# PIC32.net
KiCad netlist of a schematic drawn in EAGLE
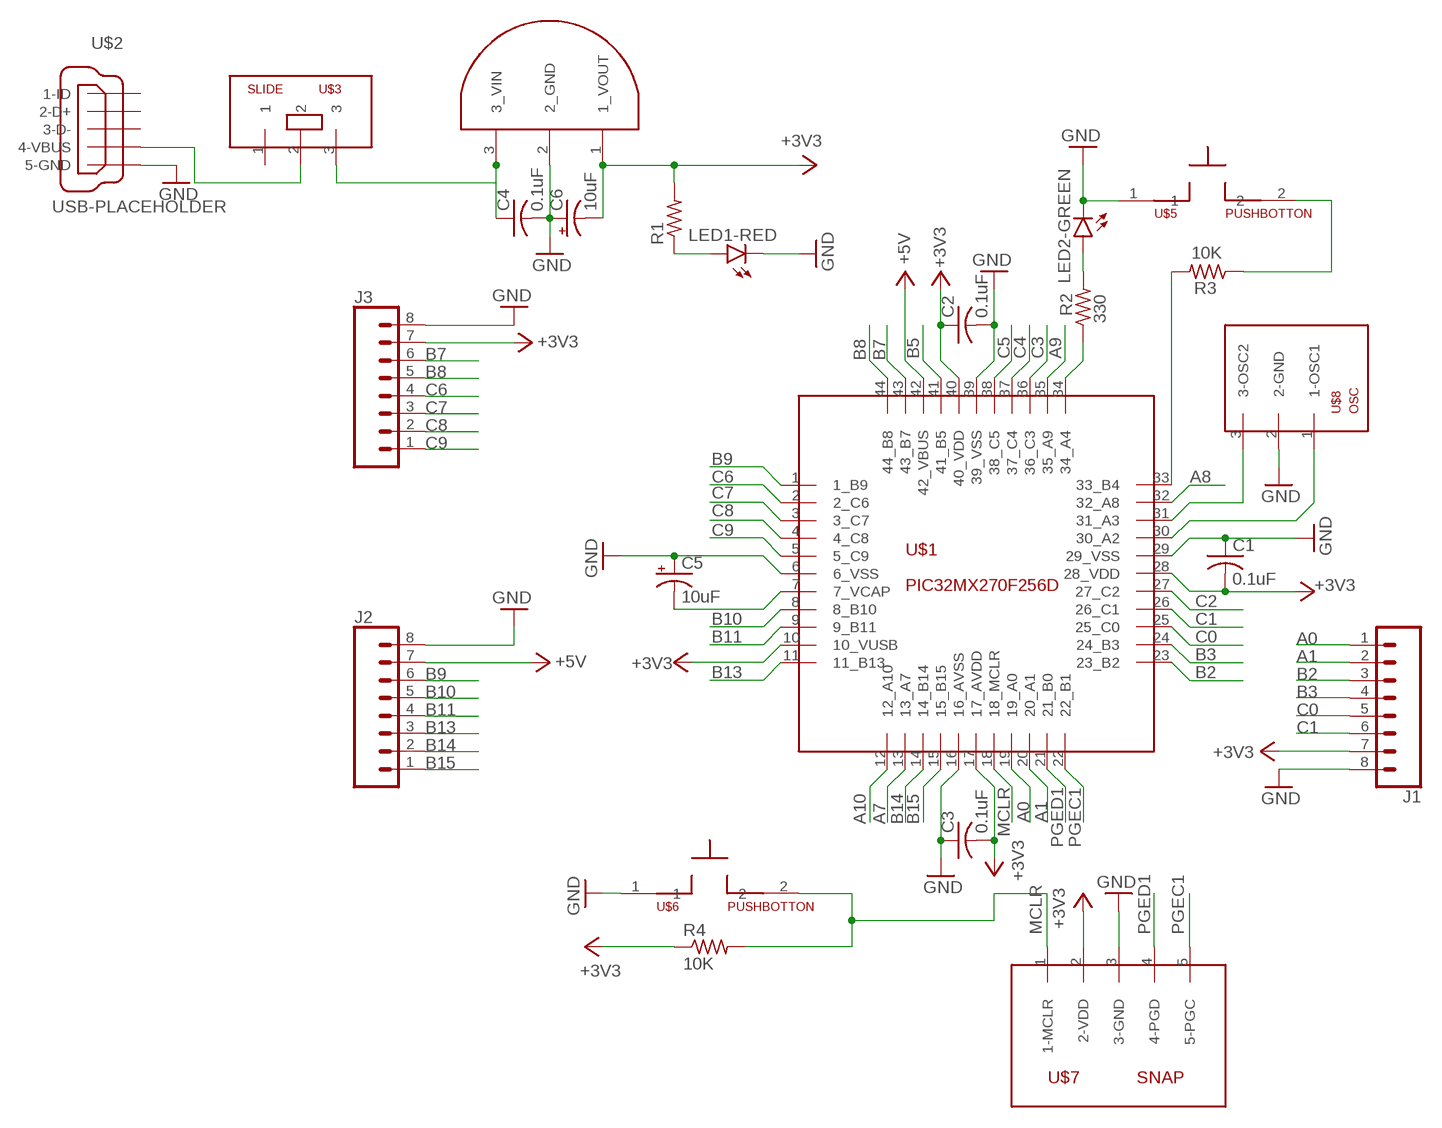
[diagram p0: schematic, sheet 1]

(export (version "E")
  (design (tool "Eeschema 10.0.6"))
  (components
    (comp (ref "C1")
      (value "0.1uF")
      (footprint "eagle-import:C025-025X050")
      (libsource (lib "eagle-import") (part "C-US025-025X050"))
    )
    (comp (ref "C2")
      (value "0.1uF")
      (footprint "eagle-import:C025-025X050")
      (libsource (lib "eagle-import") (part "C-US025-025X050"))
    )
    (comp (ref "C3")
      (value "0.1uF")
      (footprint "eagle-import:C025-025X050")
      (libsource (lib "eagle-import") (part "C-US025-025X050"))
    )
    (comp (ref "C4")
      (value "0.1uF")
      (footprint "eagle-import:C025-025X050")
      (libsource (lib "eagle-import") (part "C-US025-025X050"))
    )
    (comp (ref "C5")
      (value "10uF")
      (footprint "eagle-import:B45181B")
      (libsource (lib "eagle-import") (part "CPOL-USB45181B"))
    )
    (comp (ref "C6")
      (value "10uF")
      (footprint "eagle-import:B45181B")
      (libsource (lib "eagle-import") (part "CPOL-USB45181B"))
    )
    (comp (ref "J1")
      (value "CONN_08\"")
      (footprint "eagle-import:1X08")
      (libsource (lib "eagle-import") (part "CONN_08{dblquote}"))
    )
    (comp (ref "J2")
      (value "CONN_08\"")
      (footprint "eagle-import:1X08")
      (libsource (lib "eagle-import") (part "CONN_08{dblquote}"))
    )
    (comp (ref "J3")
      (value "CONN_08\"")
      (footprint "eagle-import:1X08")
      (libsource (lib "eagle-import") (part "CONN_08{dblquote}"))
    )
    (comp (ref "LED1-RED")
      (value "LED3MM")
      (footprint "eagle-import:LED3MM")
      (libsource (lib "eagle-import") (part "LED3MM"))
    )
    (comp (ref "LED2-GREEN")
      (value "LED3MM")
      (footprint "eagle-import:LED3MM")
      (libsource (lib "eagle-import") (part "LED3MM"))
    )
    (comp (ref "R1")
      (value "R-US_0207/10")
      (footprint "eagle-import:0207_10")
      (libsource (lib "eagle-import") (part "R-US_0207/10"))
    )
    (comp (ref "R2")
      (value "330")
      (footprint "eagle-import:0207_10")
      (libsource (lib "eagle-import") (part "R-US_0207/10"))
    )
    (comp (ref "R3")
      (value "10K")
      (footprint "eagle-import:0207_10")
      (libsource (lib "eagle-import") (part "R-US_0207/10"))
    )
    (comp (ref "R4")
      (value "10K")
      (footprint "eagle-import:0207_10")
      (libsource (lib "eagle-import") (part "R-US_0207/10"))
    )
    (comp (ref "U$1")
      (value "PIC32MX270F256D")
      (footprint "eagle-import:TQFP44")
      (libsource (lib "eagle-import") (part "PIC32MX270F256D"))
    )
    (comp (ref "U$2")
      (value "USB-PLACEHOLDER")
      (footprint "eagle-import:USB-B-MICRO-SMD_V04")
      (libsource (lib "eagle-import") (part "USB-PLACEHOLDER"))
    )
    (comp (ref "U$3")
      (value "SLIDE")
      (footprint "eagle-import:SLIDE")
      (libsource (lib "eagle-import") (part "SLIDE"))
    )
    (comp (ref "U$4")
      (value "L4931")
      (footprint "eagle-import:TO92-")
      (libsource (lib "eagle-import") (part "L4931"))
    )
    (comp (ref "U$5")
      (value "PUSHBOTTON")
      (footprint "eagle-import:PUSHBOTTON")
      (libsource (lib "eagle-import") (part "PUSHBOTTON"))
    )
    (comp (ref "U$6")
      (value "PUSHBOTTON")
      (footprint "eagle-import:PUSHBOTTON")
      (libsource (lib "eagle-import") (part "PUSHBOTTON"))
    )
    (comp (ref "U$7")
      (value "SNAP")
      (footprint "eagle-import:1X05")
      (libsource (lib "eagle-import") (part "SNAP"))
    )
    (comp (ref "U$8")
      (value "OSC")
      (footprint "eagle-import:OSC")
      (libsource (lib "eagle-import") (part "OSC"))
    )
  )
  (nets
    (net (code "1") (name "+3V3") (class "Default")
      (node (ref "C1") (pin "2") (pinfunction "2_2") (pintype "passive"))
      (node (ref "C2") (pin "1") (pinfunction "1_1") (pintype "passive"))
      (node (ref "C3") (pin "2") (pinfunction "2_2") (pintype "passive"))
      (node (ref "C6") (pin "-") (pinfunction "-_-") (pintype "passive"))
      (node (ref "J1") (pin "7") (pinfunction "7_7") (pintype "passive"))
      (node (ref "J3") (pin "7") (pinfunction "7_7") (pintype "passive"))
      (node (ref "R1") (pin "2") (pinfunction "2_2") (pintype "passive"))
      (node (ref "R4") (pin "1") (pinfunction "1_1") (pintype "passive"))
      (node (ref "U$1") (pin "10") (pinfunction "10_VUSB_10") (pintype "bidirectional"))
      (node (ref "U$1") (pin "17") (pinfunction "17_AVDD_17") (pintype "bidirectional"))
      (node (ref "U$1") (pin "28") (pinfunction "28_VDD_28") (pintype "bidirectional"))
      (node (ref "U$1") (pin "40") (pinfunction "40_VDD_40") (pintype "bidirectional"))
      (node (ref "U$4") (pin "1") (pinfunction "1_VOUT_1") (pintype "bidirectional"))
      (node (ref "U$7") (pin "2") (pinfunction "2-VDD_2") (pintype "bidirectional"))
    )
    (net (code "2") (name "+5V") (class "Default")
      (node (ref "J2") (pin "7") (pinfunction "7_7") (pintype "passive"))
      (node (ref "U$1") (pin "42") (pinfunction "42_VBUS_42") (pintype "bidirectional"))
    )
    (net (code "3") (name "/A0") (class "Default")
      (node (ref "J1") (pin "1") (pinfunction "1_1") (pintype "passive"))
      (node (ref "U$1") (pin "19") (pinfunction "19_A0_19") (pintype "bidirectional"))
    )
    (net (code "4") (name "/A1") (class "Default")
      (node (ref "J1") (pin "2") (pinfunction "2_2") (pintype "passive"))
      (node (ref "U$1") (pin "20") (pinfunction "20_A1_20") (pintype "bidirectional"))
    )
    (net (code "5") (name "/A7") (class "Default")
      (node (ref "U$1") (pin "13") (pinfunction "13_A7_13") (pintype "bidirectional"))
    )
    (net (code "6") (name "/A8") (class "Default")
      (node (ref "U$1") (pin "32") (pinfunction "32_A8_32") (pintype "bidirectional"))
    )
    (net (code "7") (name "/A9") (class "Default")
      (node (ref "U$1") (pin "35") (pinfunction "35_A9_35") (pintype "bidirectional"))
    )
    (net (code "8") (name "/A10") (class "Default")
      (node (ref "U$1") (pin "12") (pinfunction "12_A10_12") (pintype "bidirectional"))
    )
    (net (code "9") (name "/B2") (class "Default")
      (node (ref "J1") (pin "3") (pinfunction "3_3") (pintype "passive"))
      (node (ref "U$1") (pin "23") (pinfunction "23_B2_23") (pintype "bidirectional"))
    )
    (net (code "10") (name "/B3") (class "Default")
      (node (ref "J1") (pin "4") (pinfunction "4_4") (pintype "passive"))
      (node (ref "U$1") (pin "24") (pinfunction "24_B3_24") (pintype "bidirectional"))
    )
    (net (code "11") (name "/B5") (class "Default")
      (node (ref "U$1") (pin "41") (pinfunction "41_B5_41") (pintype "bidirectional"))
    )
    (net (code "12") (name "/B7") (class "Default")
      (node (ref "J3") (pin "6") (pinfunction "6_6") (pintype "passive"))
      (node (ref "U$1") (pin "43") (pinfunction "43_B7_43") (pintype "bidirectional"))
    )
    (net (code "13") (name "/B8") (class "Default")
      (node (ref "J3") (pin "5") (pinfunction "5_5") (pintype "passive"))
      (node (ref "U$1") (pin "44") (pinfunction "44_B8_44") (pintype "bidirectional"))
    )
    (net (code "14") (name "/B9") (class "Default")
      (node (ref "J2") (pin "6") (pinfunction "6_6") (pintype "passive"))
      (node (ref "U$1") (pin "1") (pinfunction "1_B9_1") (pintype "bidirectional"))
    )
    (net (code "15") (name "/B10") (class "Default")
      (node (ref "J2") (pin "5") (pinfunction "5_5") (pintype "passive"))
      (node (ref "U$1") (pin "8") (pinfunction "8_B10_8") (pintype "bidirectional"))
    )
    (net (code "16") (name "/B11") (class "Default")
      (node (ref "J2") (pin "4") (pinfunction "4_4") (pintype "passive"))
      (node (ref "U$1") (pin "9") (pinfunction "9_B11_9") (pintype "bidirectional"))
    )
    (net (code "17") (name "/B13") (class "Default")
      (node (ref "J2") (pin "3") (pinfunction "3_3") (pintype "passive"))
      (node (ref "U$1") (pin "11") (pinfunction "11_B13_11") (pintype "bidirectional"))
    )
    (net (code "18") (name "/B14") (class "Default")
      (node (ref "J2") (pin "2") (pinfunction "2_2") (pintype "passive"))
      (node (ref "U$1") (pin "14") (pinfunction "14_B14_14") (pintype "bidirectional"))
    )
    (net (code "19") (name "/B15") (class "Default")
      (node (ref "J2") (pin "1") (pinfunction "1_1") (pintype "passive"))
      (node (ref "U$1") (pin "15") (pinfunction "15_B15_15") (pintype "bidirectional"))
    )
    (net (code "20") (name "/C0") (class "Default")
      (node (ref "J1") (pin "5") (pinfunction "5_5") (pintype "passive"))
      (node (ref "U$1") (pin "25") (pinfunction "25_C0_25") (pintype "bidirectional"))
    )
    (net (code "21") (name "/C1") (class "Default")
      (node (ref "J1") (pin "6") (pinfunction "6_6") (pintype "passive"))
      (node (ref "U$1") (pin "26") (pinfunction "26_C1_26") (pintype "bidirectional"))
    )
    (net (code "22") (name "/C2") (class "Default")
      (node (ref "U$1") (pin "27") (pinfunction "27_C2_27") (pintype "bidirectional"))
    )
    (net (code "23") (name "/C3") (class "Default")
      (node (ref "U$1") (pin "36") (pinfunction "36_C3_36") (pintype "bidirectional"))
    )
    (net (code "24") (name "/C4") (class "Default")
      (node (ref "U$1") (pin "37") (pinfunction "37_C4_37") (pintype "bidirectional"))
    )
    (net (code "25") (name "/C5") (class "Default")
      (node (ref "U$1") (pin "38") (pinfunction "38_C5_38") (pintype "bidirectional"))
    )
    (net (code "26") (name "/C6") (class "Default")
      (node (ref "J3") (pin "4") (pinfunction "4_4") (pintype "passive"))
      (node (ref "U$1") (pin "2") (pinfunction "2_C6_2") (pintype "bidirectional"))
    )
    (net (code "27") (name "/C7") (class "Default")
      (node (ref "J3") (pin "3") (pinfunction "3_3") (pintype "passive"))
      (node (ref "U$1") (pin "3") (pinfunction "3_C7_3") (pintype "bidirectional"))
    )
    (net (code "28") (name "/C8") (class "Default")
      (node (ref "J3") (pin "2") (pinfunction "2_2") (pintype "passive"))
      (node (ref "U$1") (pin "4") (pinfunction "4_C8_4") (pintype "bidirectional"))
    )
    (net (code "29") (name "/C9") (class "Default")
      (node (ref "J3") (pin "1") (pinfunction "1_1") (pintype "passive"))
      (node (ref "U$1") (pin "5") (pinfunction "5_C9_5") (pintype "bidirectional"))
    )
    (net (code "30") (name "/MCLR") (class "Default")
      (node (ref "R4") (pin "2") (pinfunction "2_2") (pintype "passive"))
      (node (ref "U$1") (pin "18") (pinfunction "18_MCLR_18") (pintype "bidirectional"))
      (node (ref "U$6") (pin "2") (pinfunction "2_2") (pintype "bidirectional"))
      (node (ref "U$7") (pin "1") (pinfunction "1-MCLR_1") (pintype "bidirectional"))
    )
    (net (code "31") (name "/PGEC1") (class "Default")
      (node (ref "U$1") (pin "22") (pinfunction "22_B1_22") (pintype "bidirectional"))
      (node (ref "U$7") (pin "5") (pinfunction "5-PGC_5") (pintype "bidirectional"))
    )
    (net (code "32") (name "/PGED1") (class "Default")
      (node (ref "U$1") (pin "21") (pinfunction "21_B0_21") (pintype "bidirectional"))
      (node (ref "U$7") (pin "4") (pinfunction "4-PGD_4") (pintype "bidirectional"))
    )
    (net (code "33") (name "GND") (class "Default")
      (node (ref "C1") (pin "1") (pinfunction "1_1") (pintype "passive"))
      (node (ref "C2") (pin "2") (pinfunction "2_2") (pintype "passive"))
      (node (ref "C3") (pin "1") (pinfunction "1_1") (pintype "passive"))
      (node (ref "C4") (pin "2") (pinfunction "2_2") (pintype "passive"))
      (node (ref "C5") (pin "+") (pinfunction "+_+") (pintype "passive"))
      (node (ref "C6") (pin "+") (pinfunction "+_+") (pintype "passive"))
      (node (ref "J1") (pin "8") (pinfunction "8_8") (pintype "passive"))
      (node (ref "J2") (pin "8") (pinfunction "8_8") (pintype "passive"))
      (node (ref "J3") (pin "8") (pinfunction "8_8") (pintype "passive"))
      (node (ref "LED1-RED") (pin "K") (pinfunction "C_K") (pintype "passive"))
      (node (ref "LED2-GREEN") (pin "K") (pinfunction "C_K") (pintype "passive"))
      (node (ref "U$1") (pin "16") (pinfunction "16_AVSS_16") (pintype "bidirectional"))
      (node (ref "U$1") (pin "29") (pinfunction "29_VSS_29") (pintype "bidirectional"))
      (node (ref "U$1") (pin "39") (pinfunction "39_VSS_39") (pintype "bidirectional"))
      (node (ref "U$1") (pin "6") (pinfunction "6_VSS_6") (pintype "bidirectional"))
      (node (ref "U$2") (pin "VBUS1") (pinfunction "5-GND_VBUS1") (pintype "input"))
      (node (ref "U$4") (pin "2") (pinfunction "2_GND_2") (pintype "bidirectional"))
      (node (ref "U$5") (pin "1") (pinfunction "1_1") (pintype "bidirectional"))
      (node (ref "U$6") (pin "1") (pinfunction "1_1") (pintype "bidirectional"))
      (node (ref "U$7") (pin "3") (pinfunction "3-GND_3") (pintype "bidirectional"))
      (node (ref "U$8") (pin "2") (pinfunction "2-GND_2") (pintype "bidirectional"))
    )
    (net (code "34") (name "Net-(LED1-RED-PadA)") (class "Default")
      (node (ref "LED1-RED") (pin "A") (pinfunction "A_A") (pintype "passive"))
      (node (ref "R1") (pin "1") (pinfunction "1_1") (pintype "passive"))
    )
    (net (code "35") (name "Net-(LED2-GREEN-PadA)") (class "Default")
      (node (ref "LED2-GREEN") (pin "A") (pinfunction "A_A") (pintype "passive"))
      (node (ref "R2") (pin "2") (pinfunction "2_2") (pintype "passive"))
    )
    (net (code "36") (name "Net-(R3-Pad1)") (class "Default")
      (node (ref "R3") (pin "1") (pinfunction "1_1") (pintype "passive"))
      (node (ref "U$5") (pin "2") (pinfunction "2_2") (pintype "bidirectional"))
    )
    (net (code "37") (name "Net-(U$1-7_VCAP)") (class "Default")
      (node (ref "C5") (pin "-") (pinfunction "-_-") (pintype "passive"))
      (node (ref "U$1") (pin "7") (pinfunction "7_VCAP_7") (pintype "bidirectional"))
    )
    (net (code "38") (name "Net-(U$1-30_A2)") (class "Default")
      (node (ref "U$1") (pin "30") (pinfunction "30_A2_30") (pintype "bidirectional"))
      (node (ref "U$8") (pin "1") (pinfunction "1-OSC1_1") (pintype "bidirectional"))
    )
    (net (code "39") (name "Net-(U$1-31_A3)") (class "Default")
      (node (ref "U$1") (pin "31") (pinfunction "31_A3_31") (pintype "bidirectional"))
      (node (ref "U$8") (pin "3") (pinfunction "3-OSC2_3") (pintype "bidirectional"))
    )
    (net (code "40") (name "Net-(U$1-33_B4)") (class "Default")
      (node (ref "R3") (pin "2") (pinfunction "2_2") (pintype "passive"))
      (node (ref "U$1") (pin "33") (pinfunction "33_B4_33") (pintype "bidirectional"))
    )
    (net (code "41") (name "Net-(U$1-34_A4)") (class "Default")
      (node (ref "R2") (pin "1") (pinfunction "1_1") (pintype "passive"))
      (node (ref "U$1") (pin "34") (pinfunction "34_A4_34") (pintype "bidirectional"))
    )
    (net (code "42") (name "Net-(U$2-4-VBUS)") (class "Default")
      (node (ref "U$2") (pin "ID1") (pinfunction "4-VBUS_ID1") (pintype "input"))
      (node (ref "U$3") (pin "2") (pinfunction "2_2") (pintype "bidirectional"))
    )
    (net (code "43") (name "Net-(U$4-3_VIN)") (class "Default")
      (node (ref "C4") (pin "1") (pinfunction "1_1") (pintype "passive"))
      (node (ref "U$3") (pin "3") (pinfunction "3_3") (pintype "bidirectional"))
      (node (ref "U$4") (pin "3") (pinfunction "3_VIN_3") (pintype "bidirectional"))
    )
    (net (code "44") (name "unconnected-(U$2-1-ID-PadD+1)") (class "Default")
      (node (ref "U$2") (pin "D+1") (pinfunction "1-ID_D+1") (pintype "input"))
    )
    (net (code "45") (name "unconnected-(U$2-2-D+-PadD-1)") (class "Default")
      (node (ref "U$2") (pin "D-1") (pinfunction "2-D+_D-1") (pintype "input"))
    )
    (net (code "46") (name "unconnected-(U$2-3-D--PadGND1)") (class "Default")
      (node (ref "U$2") (pin "GND1") (pinfunction "3-D-_GND1") (pintype "input"))
    )
    (net (code "47") (name "unconnected-(U$3-Pad1)") (class "Default")
      (node (ref "U$3") (pin "1") (pinfunction "1_1") (pintype "bidirectional"))
    )
  )
)
